# Transmitter.net
KiCad netlist of a schematic drawn in Altium Designer
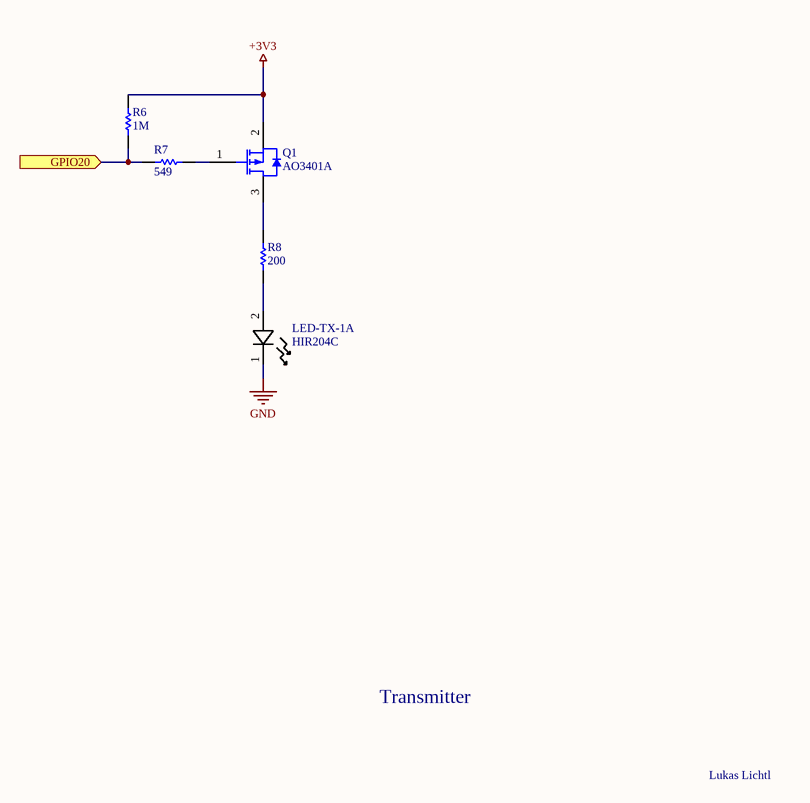
[diagram p0: Transmitter.SchDoc]

(export (version "E")
  (design (tool "Eeschema 10.0.6"))
  (components
    (comp (ref "LED-TX-1")
      (value "HIR204C")
      (footprint "LED_RADIAL_HIR204C")
      (description "Description")
      (fields (field (name "COPYRIGHT") "Copyright (C) 2025 Ultra Librarian. All rights reserved."))
      (libsource (lib "HIR204C") (part "HIR204C"))
    )
    (comp (ref "Q1")
      (value "AO3401A")
      (footprint "AO-SOT-23-3L_V")
      (description "P-Channel MOSFET, 30 V, 4 A, -55 to 150 degC, 3-Pin SOT-23-3L, RoHS, Tape and Reel")
      (fields (field (name "MANUFACTURER") "Alpha and Omega"))
      (libsource (lib "Altium Content Vault") (part "PEMOS-GSD-3"))
    )
    (comp (ref "R6")
      (value "1M")
      (footprint "RESC1608X55X25NL10T15")
      (fields (field (name "MANUFACTURER") "Yageo") (field (name "PART NUMBER") "RC0603FR-07549RL"))
      (libsource (lib "Altium Content Vault") (part "RES"))
    )
    (comp (ref "R7")
      (value "549")
      (footprint "RESC1608X55X25NL10T15")
      (fields (field (name "MANUFACTURER") "Yageo") (field (name "PART NUMBER") "RC0603FR-07549RL"))
      (libsource (lib "Altium Content Vault") (part "RES"))
    )
    (comp (ref "R8")
      (value "200")
      (footprint "RESC1608X55X25NL10T15")
      (fields (field (name "MANUFACTURER") "Yageo") (field (name "PART NUMBER") "RC0603FR-07549RL"))
      (libsource (lib "Altium Content Vault") (part "RES"))
    )
  )
  (nets
    (net (code "1") (name "+3V3") (class "Default")
      (node (ref "Q1") (pin "2") (pinfunction "SOURCE_2") (pintype "passive"))
      (node (ref "R6") (pin "2") (pinfunction "2_2") (pintype "passive"))
    )
    (net (code "2") (name "/GPIO20") (class "Default")
      (node (ref "R6") (pin "1") (pinfunction "1_1") (pintype "passive"))
      (node (ref "R7") (pin "1") (pinfunction "1_1") (pintype "passive"))
    )
    (net (code "3") (name "GND") (class "Default")
      (node (ref "LED-TX-1") (pin "1") (pinfunction "CAHTODE_1") (pintype "passive"))
    )
    (net (code "4") (name "Net-(LED-TX-1-ANODE)") (class "Default")
      (node (ref "LED-TX-1") (pin "2") (pinfunction "ANODE_2") (pintype "passive"))
      (node (ref "R8") (pin "1") (pinfunction "1_1") (pintype "passive"))
    )
    (net (code "5") (name "Net-(Q1-DRAIN)") (class "Default")
      (node (ref "Q1") (pin "3") (pinfunction "DRAIN_3") (pintype "passive"))
      (node (ref "R8") (pin "2") (pinfunction "2_2") (pintype "passive"))
    )
    (net (code "6") (name "Net-(Q1-GATE)") (class "Default")
      (node (ref "Q1") (pin "1") (pinfunction "GATE_1") (pintype "passive"))
      (node (ref "R7") (pin "2") (pinfunction "2_2") (pintype "passive"))
    )
  )
)
